# usb.net
KiCad netlist of a schematic drawn in Altium Designer
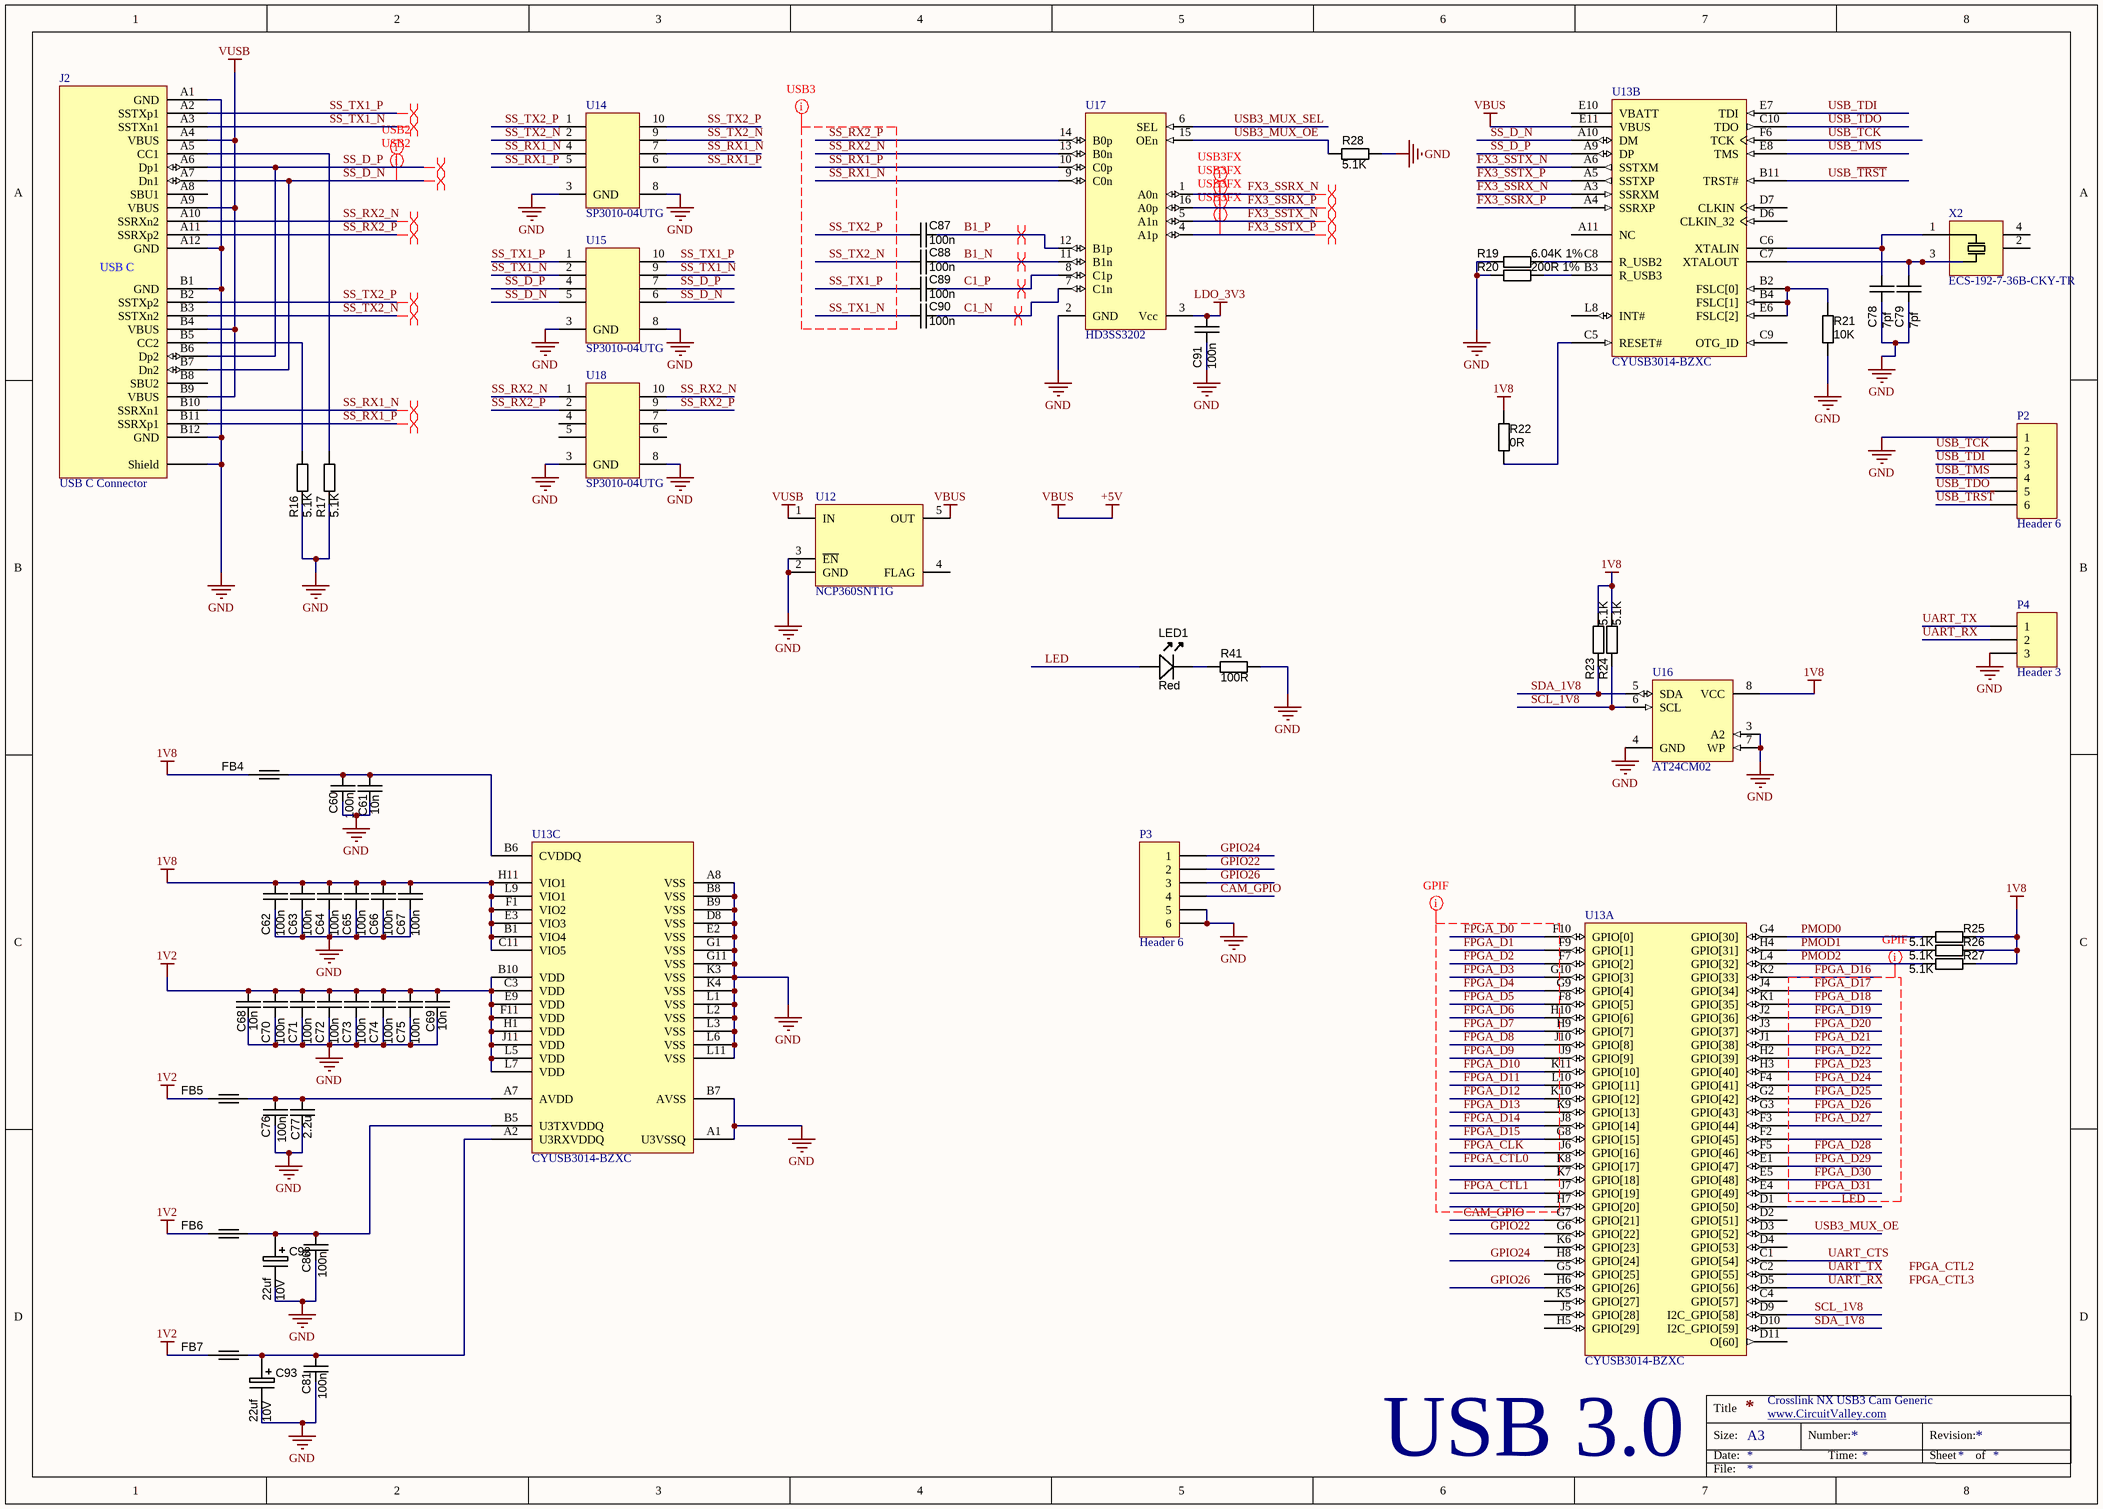
[diagram p0: usb.SchDoc]

(export (version "E")
  (design (tool "Eeschema 10.0.6"))
  (components
    (comp (ref "C60")
      (value "100n")
      (footprint "CAPC1608N")
      (description "Capacitor SMD Cer 10pF 5% 50V NP0 0603")
      (fields (field (name "TOLERANCE") "±5%") (field (name "PART") "C0603X104K5RAC"))
      (libsource (lib "PBL - Capacitors") (part "CAPC_10p_0603_NP0_1%_50V"))
    )
    (comp (ref "C61")
      (value "10n")
      (footprint "CAPC1608N")
      (description "Capacitor SMD Cer 10pF 5% 50V NP0 0603")
      (fields (field (name "TOLERANCE") "±5%") (field (name "PART") "C0603X104K5RAC"))
      (libsource (lib "PBL - Capacitors") (part "CAPC_10p_0603_NP0_1%_50V"))
    )
    (comp (ref "C62")
      (value "100n")
      (footprint "CAPC1608N")
      (description "Capacitor SMD Cer 10pF 5% 50V NP0 0603")
      (fields (field (name "TOLERANCE") "±5%") (field (name "PART") "C0603X104K5RAC"))
      (libsource (lib "PBL - Capacitors") (part "CAPC_10p_0603_NP0_1%_50V"))
    )
    (comp (ref "C63")
      (value "100n")
      (footprint "CAPC1608N")
      (description "Capacitor SMD Cer 10pF 5% 50V NP0 0603")
      (fields (field (name "TOLERANCE") "±5%") (field (name "PART") "C0603X104K5RAC"))
      (libsource (lib "PBL - Capacitors") (part "CAPC_10p_0603_NP0_1%_50V"))
    )
    (comp (ref "C64")
      (value "100n")
      (footprint "CAPC1608N")
      (description "Capacitor SMD Cer 10pF 5% 50V NP0 0603")
      (fields (field (name "TOLERANCE") "±5%") (field (name "PART") "C0603X104K5RAC"))
      (libsource (lib "PBL - Capacitors") (part "CAPC_10p_0603_NP0_1%_50V"))
    )
    (comp (ref "C65")
      (value "100n")
      (footprint "CAPC1608N")
      (description "Capacitor SMD Cer 10pF 5% 50V NP0 0603")
      (fields (field (name "TOLERANCE") "±5%") (field (name "PART") "C0603X104K5RAC"))
      (libsource (lib "PBL - Capacitors") (part "CAPC_10p_0603_NP0_1%_50V"))
    )
    (comp (ref "C66")
      (value "100n")
      (footprint "CAPC1608N")
      (description "Capacitor SMD Cer 10pF 5% 50V NP0 0603")
      (fields (field (name "TOLERANCE") "±5%") (field (name "PART") "C0603X104K5RAC"))
      (libsource (lib "PBL - Capacitors") (part "CAPC_10p_0603_NP0_1%_50V"))
    )
    (comp (ref "C67")
      (value "100n")
      (footprint "CAPC1608N")
      (description "Capacitor SMD Cer 10pF 5% 50V NP0 0603")
      (fields (field (name "TOLERANCE") "±5%") (field (name "PART") "C0603X104K5RAC"))
      (libsource (lib "PBL - Capacitors") (part "CAPC_10p_0603_NP0_1%_50V"))
    )
    (comp (ref "C68")
      (value "10n")
      (footprint "CAPC1608N")
      (description "Capacitor SMD Cer 10pF 5% 50V NP0 0603")
      (fields (field (name "TOLERANCE") "±5%") (field (name "PART") "C0603X104K5RAC"))
      (libsource (lib "PBL - Capacitors") (part "CAPC_10p_0603_NP0_1%_50V"))
    )
    (comp (ref "C69")
      (value "10n")
      (footprint "CAPC1608N")
      (description "Capacitor SMD Cer 10pF 5% 50V NP0 0603")
      (fields (field (name "TOLERANCE") "±5%") (field (name "PART") "C0603X104K5RAC"))
      (libsource (lib "PBL - Capacitors") (part "CAPC_10p_0603_NP0_1%_50V"))
    )
    (comp (ref "C70")
      (value "100n")
      (footprint "CAPC1608N")
      (description "Capacitor SMD Cer 10pF 5% 50V NP0 0603")
      (fields (field (name "TOLERANCE") "±5%") (field (name "PART") "C0603X104K5RAC"))
      (libsource (lib "PBL - Capacitors") (part "CAPC_10p_0603_NP0_1%_50V"))
    )
    (comp (ref "C71")
      (value "100n")
      (footprint "CAPC1608N")
      (description "Capacitor SMD Cer 10pF 5% 50V NP0 0603")
      (fields (field (name "TOLERANCE") "±5%") (field (name "PART") "C0603X104K5RAC"))
      (libsource (lib "PBL - Capacitors") (part "CAPC_10p_0603_NP0_1%_50V"))
    )
    (comp (ref "C72")
      (value "100n")
      (footprint "CAPC1608N")
      (description "Capacitor SMD Cer 10pF 5% 50V NP0 0603")
      (fields (field (name "TOLERANCE") "±5%") (field (name "PART") "C0603X104K5RAC"))
      (libsource (lib "PBL - Capacitors") (part "CAPC_10p_0603_NP0_1%_50V"))
    )
    (comp (ref "C73")
      (value "100n")
      (footprint "CAPC1608N")
      (description "Capacitor SMD Cer 10pF 5% 50V NP0 0603")
      (fields (field (name "TOLERANCE") "±5%") (field (name "PART") "C0603X104K5RAC"))
      (libsource (lib "PBL - Capacitors") (part "CAPC_10p_0603_NP0_1%_50V"))
    )
    (comp (ref "C74")
      (value "100n")
      (footprint "CAPC1608N")
      (description "Capacitor SMD Cer 10pF 5% 50V NP0 0603")
      (fields (field (name "TOLERANCE") "±5%") (field (name "PART") "C0603X104K5RAC"))
      (libsource (lib "PBL - Capacitors") (part "CAPC_10p_0603_NP0_1%_50V"))
    )
    (comp (ref "C75")
      (value "100n")
      (footprint "CAPC1608N")
      (description "Capacitor SMD Cer 10pF 5% 50V NP0 0603")
      (fields (field (name "TOLERANCE") "±5%") (field (name "PART") "C0603X104K5RAC"))
      (libsource (lib "PBL - Capacitors") (part "CAPC_10p_0603_NP0_1%_50V"))
    )
    (comp (ref "C76")
      (value "100n")
      (footprint "CAPC1608N")
      (description "Capacitor SMD Cer 10pF 5% 50V NP0 0603")
      (fields (field (name "TOLERANCE") "±5%") (field (name "PART") "C0603X104K5RAC"))
      (libsource (lib "PBL - Capacitors") (part "CAPC_10p_0603_NP0_1%_50V"))
    )
    (comp (ref "C77")
      (value "2.2u")
      (footprint "CAPC1608N")
      (description "Capacitor SMD Cer 10pF 5% 50V NP0 0603")
      (fields (field (name "TOLERANCE") "±5%") (field (name "PART") "C0603X104K5RAC"))
      (libsource (lib "PBL - Capacitors") (part "CAPC_10p_0603_NP0_1%_50V"))
    )
    (comp (ref "C78")
      (value "7pf")
      (footprint "CAPC1608N")
      (description "Capacitor SMD Cer 10pF 5% 50V NP0 0603")
      (fields (field (name "TOLERANCE") "±5%") (field (name "PART") "C0603X104K5RAC"))
      (libsource (lib "PBL - Capacitors") (part "CAPC_10p_0603_NP0_1%_50V"))
    )
    (comp (ref "C79")
      (value "7pf")
      (footprint "CAPC1608N")
      (description "Capacitor SMD Cer 10pF 5% 50V NP0 0603")
      (fields (field (name "TOLERANCE") "±5%") (field (name "PART") "C0603X104K5RAC"))
      (libsource (lib "PBL - Capacitors") (part "CAPC_10p_0603_NP0_1%_50V"))
    )
    (comp (ref "C80")
      (value "100n")
      (footprint "CAPC1608N")
      (description "Capacitor SMD Cer 10pF 5% 50V NP0 0603")
      (fields (field (name "TOLERANCE") "±5%") (field (name "PART") "C0603X104K5RAC"))
      (libsource (lib "PBL - Capacitors") (part "CAPC_10p_0603_NP0_1%_50V"))
    )
    (comp (ref "C81")
      (value "100n")
      (footprint "CAPC1608N")
      (description "Capacitor SMD Cer 10pF 5% 50V NP0 0603")
      (fields (field (name "TOLERANCE") "±5%") (field (name "PART") "C0603X104K5RAC"))
      (libsource (lib "PBL - Capacitors") (part "CAPC_10p_0603_NP0_1%_50V"))
    )
    (comp (ref "C87")
      (value "100n")
      (footprint "CAPC1005N")
      (description "Capacitor SMD Cer 10nF 10% 16V X7R 0402")
      (fields (field (name "TOLERANCE") "±10%"))
      (libsource (lib "PBL - Capacitors") (part "CAPC_10n_0402_16V_10%"))
    )
    (comp (ref "C88")
      (value "100n")
      (footprint "CAPC1005N")
      (description "Capacitor SMD Cer 10nF 10% 16V X7R 0402")
      (fields (field (name "TOLERANCE") "±10%"))
      (libsource (lib "PBL - Capacitors") (part "CAPC_10n_0402_16V_10%"))
    )
    (comp (ref "C89")
      (value "100n")
      (footprint "CAPC1005N")
      (description "Capacitor SMD Cer 10nF 10% 16V X7R 0402")
      (fields (field (name "TOLERANCE") "±10%"))
      (libsource (lib "PBL - Capacitors") (part "CAPC_10n_0402_16V_10%"))
    )
    (comp (ref "C90")
      (value "100n")
      (footprint "CAPC1005N")
      (description "Capacitor SMD Cer 10nF 10% 16V X7R 0402")
      (fields (field (name "TOLERANCE") "±10%"))
      (libsource (lib "PBL - Capacitors") (part "CAPC_10n_0402_16V_10%"))
    )
    (comp (ref "C91")
      (value "100n")
      (footprint "CAPC1608N")
      (description "Capacitor SMD Cer 10pF 5% 50V NP0 0603")
      (fields (field (name "TOLERANCE") "±5%") (field (name "PART") "C0603X104K5RAC"))
      (libsource (lib "PBL - Capacitors") (part "CAPC_10p_0603_NP0_1%_50V"))
    )
    (comp (ref "C92")
      (value "22uf")
      (footprint "CAPMP3528X210N")
      (description "Capacitor SMD Tantalum 47uF 20% 6.3V 1210")
      (fields (field (name "TOLERANCE") "±20%") (field (name "RATINGS") "10V"))
      (libsource (lib "PBL - Capacitors") (part "CAPT_47u_1210_6V3"))
    )
    (comp (ref "C93")
      (value "22uf")
      (footprint "CAPMP3528X210N")
      (description "Capacitor SMD Tantalum 47uF 20% 6.3V 1210")
      (fields (field (name "TOLERANCE") "±20%") (field (name "RATINGS") "10V"))
      (libsource (lib "PBL - Capacitors") (part "CAPT_47u_1210_6V3"))
    )
    (comp (ref "FB4")
      (value "~")
      (footprint "FBC2012N")
      (description "Ferrite bead 2.2K Ohm at 100 MHz 200mA 0805 SMD")
      (libsource (lib "PBL - Inductors") (part "FERRITE_0805"))
    )
    (comp (ref "FB5")
      (value "~")
      (footprint "FBC2012N")
      (description "Ferrite bead 2.2K Ohm at 100 MHz 200mA 0805 SMD")
      (libsource (lib "PBL - Inductors") (part "FERRITE_0805"))
    )
    (comp (ref "FB6")
      (value "~")
      (footprint "FBC2012N")
      (description "Ferrite bead 2.2K Ohm at 100 MHz 200mA 0805 SMD")
      (libsource (lib "PBL - Inductors") (part "FERRITE_0805"))
    )
    (comp (ref "FB7")
      (value "~")
      (footprint "FBC2012N")
      (description "Ferrite bead 2.2K Ohm at 100 MHz 200mA 0805 SMD")
      (libsource (lib "PBL - Inductors") (part "FERRITE_0805"))
    )
    (comp (ref "J2")
      (value "USB C Connector")
      (footprint "10137062-00021LF")
      (description "USB C connector")
      (libsource (lib "cvlib") (part "USB_C"))
    )
    (comp (ref "LED1")
      (value "Red")
      (footprint "LED-0603-RED")
      (description "LED 0603 SMD Hyper Red 630nm 220mcd 20mA")
      (libsource (lib "PBL - Light Sources") (part "LED_SMD_Red_0603_220mcd"))
    )
    (comp (ref "P2")
      (value "Header 6")
      (footprint "SMD_Solder_points_1.27")
      (description "Header, 6-Pin")
      (fields (field (name "PUBLISHER") "Altium Limited"))
      (libsource (lib "") (part "Header 6_1"))
    )
    (comp (ref "P3")
      (value "Header 6")
      (footprint "SMD_Solder_points_1.27")
      (description "Header, 6-Pin")
      (fields (field (name "PUBLISHER") "Altium Limited"))
      (libsource (lib "Miscellaneous Connectors") (part "Header 6"))
    )
    (comp (ref "P4")
      (value "Header 3")
      (footprint "SMD_3Solder_points_1.27")
      (description "Header, 3-Pin")
      (fields (field (name "PUBLISHER") "Altium Limited"))
      (libsource (lib "Miscellaneous Connectors") (part "Header 3"))
    )
    (comp (ref "R16")
      (value "5.1K")
      (footprint "RESC1608N_ZERO")
      (description "Resistor SMD chip 0.0 Ohm 0.1W 0603")
      (fields (field (name "TOLERANCE") "±5%") (field (name "Comment") "Thick Film"))
      (libsource (lib "") (part "RES_0R_0603_1"))
    )
    (comp (ref "R17")
      (value "5.1K")
      (footprint "RESC1608N_ZERO")
      (description "Resistor SMD chip 0.0 Ohm 0.1W 0603")
      (fields (field (name "TOLERANCE") "±5%") (field (name "Comment") "Thick Film"))
      (libsource (lib "") (part "RES_0R_0603_1"))
    )
    (comp (ref "R19")
      (value "6.04K 1%")
      (footprint "RESC1608N_ZERO")
      (description "Resistor SMD chip 0.0 Ohm 0.1W 0603")
      (fields (field (name "TOLERANCE") "±5%") (field (name "Comment") "Thick Film"))
      (libsource (lib "PBL - Resistors") (part "RES_0R_0603"))
    )
    (comp (ref "R20")
      (value "200R 1%")
      (footprint "RESC1608N_ZERO")
      (description "Resistor SMD chip 0.0 Ohm 0.1W 0603")
      (fields (field (name "TOLERANCE") "±5%") (field (name "Comment") "Thick Film"))
      (libsource (lib "PBL - Resistors") (part "RES_0R_0603"))
    )
    (comp (ref "R21")
      (value "10K")
      (footprint "RESC1608N_ZERO")
      (description "Resistor SMD chip 0.0 Ohm 0.1W 0603")
      (fields (field (name "TOLERANCE") "±5%") (field (name "Comment") "Thick Film"))
      (libsource (lib "") (part "RES_0R_0603_1"))
    )
    (comp (ref "R22")
      (value "0R")
      (footprint "RESC1608N_ZERO")
      (description "Resistor SMD chip 0.0 Ohm 0.1W 0603")
      (fields (field (name "TOLERANCE") "±5%") (field (name "Comment") "Thick Film"))
      (libsource (lib "") (part "RES_0R_0603_3"))
    )
    (comp (ref "R23")
      (value "5.1K")
      (footprint "RESC1608N_ZERO")
      (description "Resistor SMD chip 0.0 Ohm 0.1W 0603")
      (fields (field (name "TOLERANCE") "±5%") (field (name "Comment") "Thick Film"))
      (libsource (lib "") (part "RES_0R_0603_3"))
    )
    (comp (ref "R24")
      (value "5.1K")
      (footprint "RESC1608N_ZERO")
      (description "Resistor SMD chip 0.0 Ohm 0.1W 0603")
      (fields (field (name "TOLERANCE") "±5%") (field (name "Comment") "Thick Film"))
      (libsource (lib "") (part "RES_0R_0603_1"))
    )
    (comp (ref "R25")
      (value "5.1K")
      (footprint "RESC1608N_ZERO")
      (description "Resistor SMD chip 0.0 Ohm 0.1W 0603")
      (fields (field (name "TOLERANCE") "±5%") (field (name "Comment") "Thick Film"))
      (libsource (lib "") (part "RES_0R_0603_2"))
    )
    (comp (ref "R26")
      (value "5.1K")
      (footprint "RESC1608N_ZERO")
      (description "Resistor SMD chip 0.0 Ohm 0.1W 0603")
      (fields (field (name "TOLERANCE") "±5%") (field (name "Comment") "Thick Film"))
      (libsource (lib "") (part "RES_0R_0603_2"))
    )
    (comp (ref "R27")
      (value "5.1K")
      (footprint "RESC1608N_ZERO")
      (description "Resistor SMD chip 0.0 Ohm 0.1W 0603")
      (fields (field (name "TOLERANCE") "±5%") (field (name "Comment") "Thick Film"))
      (libsource (lib "") (part "RES_0R_0603_2"))
    )
    (comp (ref "R28")
      (value "5.1K")
      (footprint "RESC1608N_ZERO")
      (description "Resistor SMD chip 0.0 Ohm 0.1W 0603")
      (fields (field (name "TOLERANCE") "±5%") (field (name "Comment") "Thick Film"))
      (libsource (lib "") (part "RES_0R_0603_2"))
    )
    (comp (ref "R41")
      (value "100R")
      (footprint "RESC1608N_ZERO")
      (description "Resistor SMD chip 0.0 Ohm 0.1W 0603")
      (fields (field (name "TOLERANCE") "±5%") (field (name "Comment") "Thick Film"))
      (libsource (lib "") (part "RES_0R_0603_2"))
    )
    (comp (ref "U12")
      (value "NCP360SNT1G")
      (footprint "SOT23-5")
      (description "USB Overvoltage Protection")
      (libsource (lib "cvlib") (part "NCP360SNT1G"))
    )
    (comp (ref "U13")
      (value "CYUSB3014-BZXC")
      (footprint "CYP-BZX121")
      (description "EZ-USB(R) FX3: SuperSpeed USB Controller, 512 KB, 60 I/Os, 0 to 70 degC, 121-Pin FBGA (BZX121)")
      (fields (field (name "MANUFACTURER") "Cypress"))
      (libsource (lib "") (part "CYUSB3014-BZXC_1"))
    )
    (comp (ref "U14")
      (value "SP3010-04UTG")
      (footprint "uDFN-10")
      (description "ESD Protection")
      (libsource (lib "cvlib") (part "SP3010-04UTG"))
    )
    (comp (ref "U15")
      (value "SP3010-04UTG")
      (footprint "uDFN-10")
      (description "ESD Protection")
      (libsource (lib "cvlib") (part "SP3010-04UTG"))
    )
    (comp (ref "U16")
      (value "AT24CM02")
      (footprint "SOIC8")
      (description "2Mbit I2C EEPROM")
      (libsource (lib "cvlib") (part "AT24CM02"))
    )
    (comp (ref "U17")
      (value "HD3SS3202")
      (footprint "UQFN-16")
      (description "USB 3.0 Mux")
      (libsource (lib "cvlib") (part "HD3SS3202"))
    )
    (comp (ref "U18")
      (value "SP3010-04UTG")
      (footprint "uDFN-10")
      (description "ESD Protection")
      (libsource (lib "cvlib") (part "SP3010-04UTG"))
    )
    (comp (ref "X2")
      (value "ECS-192-7-36B-CKY-TR")
      (footprint "Active Oscillator 2520")
      (description "Crystal Oscillator")
      (libsource (lib "cvlib") (part "Crystal"))
    )
  )
  (nets
    (net (code "1") (name "+5V") (class "Default")
      (node (ref "U12") (pin "5") (pinfunction "OUT_5") (pintype "power_in"))
      (node (ref "U13") (pin "E11") (pinfunction "VBUS_E11") (pintype "power_in"))
    )
    (net (code "2") (name "/B1_N") (class "Default")
      (node (ref "C88") (pin "2") (pintype "passive"))
      (node (ref "U17") (pin "11") (pinfunction "B1n_11") (pintype "bidirectional"))
    )
    (net (code "3") (name "/B1_P") (class "Default")
      (node (ref "C87") (pin "2") (pintype "passive"))
      (node (ref "U17") (pin "12") (pinfunction "B1p_12") (pintype "bidirectional"))
    )
    (net (code "4") (name "/C1_N") (class "Default")
      (node (ref "C90") (pin "2") (pintype "passive"))
      (node (ref "U17") (pin "7") (pinfunction "C1n_7") (pintype "bidirectional"))
    )
    (net (code "5") (name "/C1_P") (class "Default")
      (node (ref "C89") (pin "2") (pintype "passive"))
      (node (ref "U17") (pin "8") (pinfunction "C1p_8") (pintype "bidirectional"))
    )
    (net (code "6") (name "/CAM_GPIO") (class "Default")
      (node (ref "P3") (pin "4") (pinfunction "4_4") (pintype "passive"))
      (node (ref "U13") (pin "G7") (pinfunction "GPIO[21]_G7") (pintype "bidirectional"))
    )
    (net (code "7") (name "/FPGA_CLK") (class "Default")
      (node (ref "U13") (pin "J6") (pinfunction "GPIO[16]_J6") (pintype "bidirectional"))
    )
    (net (code "8") (name "/FPGA_CTL0") (class "Default")
      (node (ref "U13") (pin "K8") (pinfunction "GPIO[17]_K8") (pintype "bidirectional"))
    )
    (net (code "9") (name "/FPGA_CTL1") (class "Default")
      (node (ref "U13") (pin "J7") (pinfunction "GPIO[19]_J7") (pintype "bidirectional"))
    )
    (net (code "12") (name "/FPGA_D0") (class "Default")
      (node (ref "U13") (pin "F10") (pinfunction "GPIO[0]_F10") (pintype "bidirectional"))
    )
    (net (code "13") (name "/FPGA_D1") (class "Default")
      (node (ref "U13") (pin "F9") (pinfunction "GPIO[1]_F9") (pintype "bidirectional"))
    )
    (net (code "14") (name "/FPGA_D2") (class "Default")
      (node (ref "U13") (pin "F7") (pinfunction "GPIO[2]_F7") (pintype "bidirectional"))
    )
    (net (code "15") (name "/FPGA_D3") (class "Default")
      (node (ref "U13") (pin "G10") (pinfunction "GPIO[3]_G10") (pintype "bidirectional"))
    )
    (net (code "16") (name "/FPGA_D4") (class "Default")
      (node (ref "U13") (pin "G9") (pinfunction "GPIO[4]_G9") (pintype "bidirectional"))
    )
    (net (code "17") (name "/FPGA_D5") (class "Default")
      (node (ref "U13") (pin "F8") (pinfunction "GPIO[5]_F8") (pintype "bidirectional"))
    )
    (net (code "18") (name "/FPGA_D6") (class "Default")
      (node (ref "U13") (pin "H10") (pinfunction "GPIO[6]_H10") (pintype "bidirectional"))
    )
    (net (code "19") (name "/FPGA_D7") (class "Default")
      (node (ref "U13") (pin "H9") (pinfunction "GPIO[7]_H9") (pintype "bidirectional"))
    )
    (net (code "20") (name "/FPGA_D8") (class "Default")
      (node (ref "U13") (pin "J10") (pinfunction "GPIO[8]_J10") (pintype "bidirectional"))
    )
    (net (code "21") (name "/FPGA_D9") (class "Default")
      (node (ref "U13") (pin "J9") (pinfunction "GPIO[9]_J9") (pintype "bidirectional"))
    )
    (net (code "22") (name "/FPGA_D10") (class "Default")
      (node (ref "U13") (pin "K11") (pinfunction "GPIO[10]_K11") (pintype "bidirectional"))
    )
    (net (code "23") (name "/FPGA_D11") (class "Default")
      (node (ref "U13") (pin "L10") (pinfunction "GPIO[11]_L10") (pintype "bidirectional"))
    )
    (net (code "24") (name "/FPGA_D12") (class "Default")
      (node (ref "U13") (pin "K10") (pinfunction "GPIO[12]_K10") (pintype "bidirectional"))
    )
    (net (code "25") (name "/FPGA_D13") (class "Default")
      (node (ref "U13") (pin "K9") (pinfunction "GPIO[13]_K9") (pintype "bidirectional"))
    )
    (net (code "26") (name "/FPGA_D14") (class "Default")
      (node (ref "U13") (pin "J8") (pinfunction "GPIO[14]_J8") (pintype "bidirectional"))
    )
    (net (code "27") (name "/FPGA_D15") (class "Default")
      (node (ref "U13") (pin "G8") (pinfunction "GPIO[15]_G8") (pintype "bidirectional"))
    )
    (net (code "28") (name "/FPGA_D16") (class "Default")
      (node (ref "U13") (pin "K2") (pinfunction "GPIO[33]_K2") (pintype "bidirectional"))
    )
    (net (code "29") (name "/FPGA_D17") (class "Default")
      (node (ref "U13") (pin "J4") (pinfunction "GPIO[34]_J4") (pintype "bidirectional"))
    )
    (net (code "30") (name "/FPGA_D18") (class "Default")
      (node (ref "U13") (pin "K1") (pinfunction "GPIO[35]_K1") (pintype "bidirectional"))
    )
    (net (code "31") (name "/FPGA_D19") (class "Default")
      (node (ref "U13") (pin "J2") (pinfunction "GPIO[36]_J2") (pintype "bidirectional"))
    )
    (net (code "32") (name "/FPGA_D20") (class "Default")
      (node (ref "U13") (pin "J3") (pinfunction "GPIO[37]_J3") (pintype "bidirectional"))
    )
    (net (code "33") (name "/FPGA_D21") (class "Default")
      (node (ref "U13") (pin "J1") (pinfunction "GPIO[38]_J1") (pintype "bidirectional"))
    )
    (net (code "34") (name "/FPGA_D22") (class "Default")
      (node (ref "U13") (pin "H2") (pinfunction "GPIO[39]_H2") (pintype "bidirectional"))
    )
    (net (code "35") (name "/FPGA_D23") (class "Default")
      (node (ref "U13") (pin "H3") (pinfunction "GPIO[40]_H3") (pintype "bidirectional"))
    )
    (net (code "36") (name "/FPGA_D24") (class "Default")
      (node (ref "U13") (pin "F4") (pinfunction "GPIO[41]_F4") (pintype "bidirectional"))
    )
    (net (code "37") (name "/FPGA_D25") (class "Default")
      (node (ref "U13") (pin "G2") (pinfunction "GPIO[42]_G2") (pintype "bidirectional"))
    )
    (net (code "38") (name "/FPGA_D26") (class "Default")
      (node (ref "U13") (pin "G3") (pinfunction "GPIO[43]_G3") (pintype "bidirectional"))
    )
    (net (code "39") (name "/FPGA_D27") (class "Default")
      (node (ref "U13") (pin "F3") (pinfunction "GPIO[44]_F3") (pintype "bidirectional"))
    )
    (net (code "40") (name "/FPGA_D28") (class "Default")
      (node (ref "U13") (pin "F5") (pinfunction "GPIO[46]_F5") (pintype "bidirectional"))
    )
    (net (code "41") (name "/FPGA_D29") (class "Default")
      (node (ref "U13") (pin "E1") (pinfunction "GPIO[47]_E1") (pintype "bidirectional"))
    )
    (net (code "42") (name "/FPGA_D30") (class "Default")
      (node (ref "U13") (pin "E5") (pinfunction "GPIO[48]_E5") (pintype "bidirectional"))
    )
    (net (code "43") (name "/FPGA_D31") (class "Default")
      (node (ref "U13") (pin "E4") (pinfunction "GPIO[49]_E4") (pintype "bidirectional"))
    )
    (net (code "44") (name "/FX3_SSRX_N") (class "Default")
      (node (ref "U13") (pin "A3") (pinfunction "SSRXM_A3") (pintype "input"))
      (node (ref "U17") (pin "1") (pinfunction "A0n_1") (pintype "bidirectional"))
    )
    (net (code "45") (name "/FX3_SSRX_P") (class "Default")
      (node (ref "U13") (pin "A4") (pinfunction "SSRXP_A4") (pintype "input"))
      (node (ref "U17") (pin "16") (pinfunction "A0p_16") (pintype "bidirectional"))
    )
    (net (code "46") (name "/FX3_SSTX_N") (class "Default")
      (node (ref "U13") (pin "A6") (pinfunction "SSTXM_A6") (pintype "output"))
      (node (ref "U17") (pin "5") (pinfunction "A1n_5") (pintype "bidirectional"))
    )
    (net (code "47") (name "/FX3_SSTX_P") (class "Default")
      (node (ref "U13") (pin "A5") (pinfunction "SSTXP_A5") (pintype "output"))
      (node (ref "U17") (pin "4") (pinfunction "A1p_4") (pintype "bidirectional"))
    )
    (net (code "48") (name "/GPIO22") (class "Default")
      (node (ref "P3") (pin "2") (pinfunction "2_2") (pintype "passive"))
      (node (ref "U13") (pin "G6") (pinfunction "GPIO[22]_G6") (pintype "bidirectional"))
    )
    (net (code "49") (name "/GPIO24") (class "Default")
      (node (ref "P3") (pin "1") (pinfunction "1_1") (pintype "passive"))
      (node (ref "U13") (pin "H8") (pinfunction "GPIO[24]_H8") (pintype "bidirectional"))
    )
    (net (code "50") (name "/GPIO26") (class "Default")
      (node (ref "P3") (pin "3") (pinfunction "3_3") (pintype "passive"))
      (node (ref "U13") (pin "H6") (pinfunction "GPIO[26]_H6") (pintype "bidirectional"))
    )
    (net (code "51") (name "/LED") (class "Default")
      (node (ref "LED1") (pin "A") (pinfunction "A_A") (pintype "passive"))
      (node (ref "U13") (pin "D1") (pinfunction "GPIO[50]_D1") (pintype "bidirectional"))
    )
    (net (code "52") (name "/PMOD0") (class "Default")
      (node (ref "R25") (pin "1") (pinfunction "1_1") (pintype "passive"))
      (node (ref "U13") (pin "G4") (pinfunction "GPIO[30]_G4") (pintype "bidirectional"))
    )
    (net (code "53") (name "/PMOD1") (class "Default")
      (node (ref "R26") (pin "1") (pinfunction "1_1") (pintype "passive"))
      (node (ref "U13") (pin "H4") (pinfunction "GPIO[31]_H4") (pintype "bidirectional"))
    )
    (net (code "54") (name "/PMOD2") (class "Default")
      (node (ref "R27") (pin "1") (pinfunction "1_1") (pintype "passive"))
      (node (ref "U13") (pin "L4") (pinfunction "GPIO[32]_L4") (pintype "bidirectional"))
    )
    (net (code "55") (name "/SCL_1V8") (class "Default")
      (node (ref "R24") (pin "2") (pinfunction "2_2") (pintype "passive"))
      (node (ref "U13") (pin "D9") (pinfunction "I2C_GPIO[58]_D9") (pintype "bidirectional"))
      (node (ref "U16") (pin "6") (pinfunction "SCL_6") (pintype "input"))
    )
    (net (code "56") (name "/SDA_1V8") (class "Default")
      (node (ref "R23") (pin "1") (pinfunction "1_1") (pintype "passive"))
      (node (ref "U13") (pin "D10") (pinfunction "I2C_GPIO[59]_D10") (pintype "bidirectional"))
      (node (ref "U16") (pin "5") (pinfunction "SDA_5") (pintype "bidirectional"))
    )
    (net (code "57") (name "/SS_D_N") (class "Default")
      (node (ref "J2") (pin "A7") (pinfunction "Dn1_A7") (pintype "bidirectional"))
      (node (ref "J2") (pin "B7") (pinfunction "Dn2_B7") (pintype "bidirectional"))
      (node (ref "U13") (pin "A10") (pinfunction "DM_A10") (pintype "bidirectional"))
      (node (ref "U15") (pin "5") (pintype "passive"))
      (node (ref "U15") (pin "6") (pintype "passive"))
    )
    (net (code "58") (name "/SS_D_P") (class "Default")
      (node (ref "J2") (pin "A6") (pinfunction "Dp1_A6") (pintype "bidirectional"))
      (node (ref "J2") (pin "B6") (pinfunction "Dp2_B6") (pintype "bidirectional"))
      (node (ref "U13") (pin "A9") (pinfunction "DP_A9") (pintype "bidirectional"))
      (node (ref "U15") (pin "4") (pintype "passive"))
      (node (ref "U15") (pin "7") (pintype "passive"))
    )
    (net (code "59") (name "/SS_RX1_N") (class "Default")
      (node (ref "J2") (pin "B10") (pinfunction "SSRXn1_B10") (pintype "passive"))
      (node (ref "U14") (pin "4") (pintype "passive"))
      (node (ref "U14") (pin "7") (pintype "passive"))
      (node (ref "U17") (pin "9") (pinfunction "C0n_9") (pintype "bidirectional"))
    )
    (net (code "60") (name "/SS_RX1_P") (class "Default")
      (node (ref "J2") (pin "B11") (pinfunction "SSRXp1_B11") (pintype "passive"))
      (node (ref "U14") (pin "5") (pintype "passive"))
      (node (ref "U14") (pin "6") (pintype "passive"))
      (node (ref "U17") (pin "10") (pinfunction "C0p_10") (pintype "bidirectional"))
    )
    (net (code "61") (name "/SS_RX2_N") (class "Default")
      (node (ref "J2") (pin "A10") (pinfunction "SSRXn2_A10") (pintype "passive"))
      (node (ref "U17") (pin "13") (pinfunction "B0n_13") (pintype "bidirectional"))
      (node (ref "U18") (pin "1") (pintype "passive"))
      (node (ref "U18") (pin "10") (pintype "passive"))
    )
    (net (code "62") (name "/SS_RX2_P") (class "Default")
      (node (ref "J2") (pin "A11") (pinfunction "SSRXp2_A11") (pintype "passive"))
      (node (ref "U17") (pin "14") (pinfunction "B0p_14") (pintype "bidirectional"))
      (node (ref "U18") (pin "2") (pintype "passive"))
      (node (ref "U18") (pin "9") (pintype "passive"))
    )
    (net (code "63") (name "/SS_TX1_N") (class "Default")
      (node (ref "C90") (pin "1") (pintype "passive"))
      (node (ref "J2") (pin "A3") (pinfunction "SSTXn1_A3") (pintype "passive"))
      (node (ref "U15") (pin "2") (pintype "passive"))
      (node (ref "U15") (pin "9") (pintype "passive"))
    )
    (net (code "64") (name "/SS_TX1_P") (class "Default")
      (node (ref "C89") (pin "1") (pintype "passive"))
      (node (ref "J2") (pin "A2") (pinfunction "SSTXp1_A2") (pintype "passive"))
      (node (ref "U15") (pin "1") (pintype "passive"))
      (node (ref "U15") (pin "10") (pintype "passive"))
    )
    (net (code "65") (name "/SS_TX2_N") (class "Default")
      (node (ref "C88") (pin "1") (pintype "passive"))
      (node (ref "J2") (pin "B3") (pinfunction "SSTXn2_B3") (pintype "passive"))
      (node (ref "U14") (pin "2") (pintype "passive"))
      (node (ref "U14") (pin "9") (pintype "passive"))
    )
    (net (code "66") (name "/SS_TX2_P") (class "Default")
      (node (ref "C87") (pin "1") (pintype "passive"))
      (node (ref "J2") (pin "B2") (pinfunction "SSTXp2_B2") (pintype "passive"))
      (node (ref "U14") (pin "1") (pintype "passive"))
      (node (ref "U14") (pin "10") (pintype "passive"))
    )
    (net (code "67") (name "/UART_CTS") (class "Default")
      (node (ref "U13") (pin "C1") (pinfunction "GPIO[54]_C1") (pintype "bidirectional"))
    )
    (net (code "68") (name "/UART_RX") (class "Default")
      (node (ref "P4") (pin "2") (pinfunction "2_2") (pintype "passive"))
      (node (ref "U13") (pin "D5") (pinfunction "GPIO[56]_D5") (pintype "bidirectional"))
    )
    (net (code "69") (name "/UART_TX") (class "Default")
      (node (ref "P4") (pin "1") (pinfunction "1_1") (pintype "passive"))
      (node (ref "U13") (pin "C2") (pinfunction "GPIO[55]_C2") (pintype "bidirectional"))
    )
    (net (code "70") (name "/USB3_MUX_OE") (class "Default")
      (node (ref "R28") (pin "1") (pinfunction "1_1") (pintype "passive"))
      (node (ref "U13") (pin "D3") (pinfunction "GPIO[52]_D3") (pintype "bidirectional"))
      (node (ref "U17") (pin "15") (pinfunction "OEn_15") (pintype "input"))
    )
    (net (code "71") (name "/USB3_MUX_SEL") (class "Default")
      (node (ref "U17") (pin "6") (pinfunction "SEL_6") (pintype "input"))
    )
    (net (code "72") (name "/USB_TCK") (class "Default")
      (node (ref "P2") (pin "2") (pinfunction "2_2") (pintype "passive"))
      (node (ref "U13") (pin "F6") (pinfunction "TCK_F6") (pintype "input"))
    )
    (net (code "73") (name "/USB_TDI") (class "Default")
      (node (ref "P2") (pin "3") (pinfunction "3_3") (pintype "passive"))
      (node (ref "U13") (pin "E7") (pinfunction "TDI_E7") (pintype "input"))
    )
    (net (code "74") (name "/USB_TDO") (class "Default")
      (node (ref "P2") (pin "5") (pinfunction "5_5") (pintype "passive"))
      (node (ref "U13") (pin "C10") (pinfunction "TDO_C10") (pintype "output"))
    )
    (net (code "75") (name "/USB_TMS") (class "Default")
      (node (ref "P2") (pin "4") (pinfunction "4_4") (pintype "passive"))
      (node (ref "U13") (pin "E8") (pinfunction "TMS_E8") (pintype "input"))
    )
    (net (code "76") (name "/USB_~{TRST}") (class "Default")
      (node (ref "P2") (pin "6") (pinfunction "6_6") (pintype "passive"))
      (node (ref "U13") (pin "B11") (pinfunction "TRST#_B11") (pintype "input"))
    )
    (net (code "77") (name "1V2") (class "Default")
      (node (ref "C68") (pin "2") (pintype "passive"))
      (node (ref "C69") (pin "2") (pintype "passive"))
      (node (ref "C70") (pin "2") (pintype "passive"))
      (node (ref "C71") (pin "2") (pintype "passive"))
      (node (ref "C72") (pin "2") (pintype "passive"))
      (node (ref "C73") (pin "2") (pintype "passive"))
      (node (ref "C74") (pin "2") (pintype "passive"))
      (node (ref "C75") (pin "2") (pintype "passive"))
      (node (ref "FB5") (pin "1") (pinfunction "1_1") (pintype "passive"))
      (node (ref "FB6") (pin "1") (pinfunction "1_1") (pintype "passive"))
      (node (ref "FB7") (pin "1") (pinfunction "1_1") (pintype "passive"))
      (node (ref "U13") (pin "B10") (pinfunction "VDD_B10") (pintype "power_in"))
      (node (ref "U13") (pin "C3") (pinfunction "VDD_C3") (pintype "power_in"))
      (node (ref "U13") (pin "E9") (pinfunction "VDD_E9") (pintype "power_in"))
      (node (ref "U13") (pin "F11") (pinfunction "VDD_F11") (pintype "power_in"))
      (node (ref "U13") (pin "H1") (pinfunction "VDD_H1") (pintype "power_in"))
      (node (ref "U13") (pin "J11") (pinfunction "VDD_J11") (pintype "power_in"))
      (node (ref "U13") (pin "L5") (pinfunction "VDD_L5") (pintype "power_in"))
      (node (ref "U13") (pin "L7") (pinfunction "VDD_L7") (pintype "power_in"))
    )
    (net (code "78") (name "1V8") (class "Default")
      (node (ref "C62") (pin "2") (pintype "passive"))
      (node (ref "C63") (pin "2") (pintype "passive"))
      (node (ref "C64") (pin "2") (pintype "passive"))
      (node (ref "C65") (pin "2") (pintype "passive"))
      (node (ref "C66") (pin "2") (pintype "passive"))
      (node (ref "C67") (pin "2") (pintype "passive"))
      (node (ref "FB4") (pin "1") (pinfunction "1_1") (pintype "passive"))
      (node (ref "R22") (pin "2") (pinfunction "2_2") (pintype "passive"))
      (node (ref "R23") (pin "2") (pinfunction "2_2") (pintype "passive"))
      (node (ref "R24") (pin "1") (pinfunction "1_1") (pintype "passive"))
      (node (ref "R25") (pin "2") (pinfunction "2_2") (pintype "passive"))
      (node (ref "R26") (pin "2") (pinfunction "2_2") (pintype "passive"))
      (node (ref "R27") (pin "2") (pinfunction "2_2") (pintype "passive"))
      (node (ref "U13") (pin "B1") (pinfunction "VIO4_B1") (pintype "power_in"))
      (node (ref "U13") (pin "C11") (pinfunction "VIO5_C11") (pintype "power_in"))
      (node (ref "U13") (pin "E3") (pinfunction "VIO3_E3") (pintype "power_in"))
      (node (ref "U13") (pin "F1") (pinfunction "VIO2_F1") (pintype "power_in"))
      (node (ref "U13") (pin "H11") (pinfunction "VIO1_H11") (pintype "power_in"))
      (node (ref "U13") (pin "L9") (pinfunction "VIO1_L9") (pintype "power_in"))
      (node (ref "U16") (pin "8") (pinfunction "VCC_8") (pintype "power_in"))
    )
    (net (code "79") (name "GND") (class "Default")
      (node (ref "C60") (pin "1") (pintype "passive"))
      (node (ref "C61") (pin "1") (pintype "passive"))
      (node (ref "C62") (pin "1") (pintype "passive"))
      (node (ref "C63") (pin "1") (pintype "passive"))
      (node (ref "C64") (pin "1") (pintype "passive"))
      (node (ref "C65") (pin "1") (pintype "passive"))
      (node (ref "C66") (pin "1") (pintype "passive"))
      (node (ref "C67") (pin "1") (pintype "passive"))
      (node (ref "C68") (pin "1") (pintype "passive"))
      (node (ref "C69") (pin "1") (pintype "passive"))
      (node (ref "C70") (pin "1") (pintype "passive"))
      (node (ref "C71") (pin "1") (pintype "passive"))
      (node (ref "C72") (pin "1") (pintype "passive"))
      (node (ref "C73") (pin "1") (pintype "passive"))
      (node (ref "C74") (pin "1") (pintype "passive"))
      (node (ref "C75") (pin "1") (pintype "passive"))
      (node (ref "C76") (pin "1") (pintype "passive"))
      (node (ref "C77") (pin "1") (pintype "passive"))
      (node (ref "C78") (pin "1") (pintype "passive"))
      (node (ref "C79") (pin "1") (pintype "passive"))
      (node (ref "C80") (pin "1") (pintype "passive"))
      (node (ref "C81") (pin "1") (pintype "passive"))
      (node (ref "C91") (pin "1") (pintype "passive"))
      (node (ref "C92") (pin "2") (pintype "passive"))
      (node (ref "C93") (pin "2") (pintype "passive"))
      (node (ref "J2") (pin "0") (pinfunction "Shield_0") (pintype "power_in"))
      (node (ref "J2") (pin "A1") (pinfunction "GND_A1") (pintype "power_in"))
      (node (ref "J2") (pin "A12") (pinfunction "GND_A12") (pintype "power_in"))
      (node (ref "J2") (pin "B1") (pinfunction "GND_B1") (pintype "power_in"))
      (node (ref "J2") (pin "B12") (pinfunction "GND_B12") (pintype "power_in"))
      (node (ref "P2") (pin "1") (pinfunction "1_1") (pintype "passive"))
      (node (ref "P3") (pin "5") (pinfunction "5_5") (pintype "passive"))
      (node (ref "P3") (pin "6") (pinfunction "6_6") (pintype "passive"))
      (node (ref "P4") (pin "3") (pinfunction "3_3") (pintype "passive"))
      (node (ref "R16") (pin "2") (pinfunction "2_2") (pintype "passive"))
      (node (ref "R17") (pin "2") (pinfunction "2_2") (pintype "passive"))
      (node (ref "R19") (pin "2") (pinfunction "2_2") (pintype "passive"))
      (node (ref "R20") (pin "2") (pinfunction "2_2") (pintype "passive"))
      (node (ref "R21") (pin "2") (pinfunction "2_2") (pintype "passive"))
      (node (ref "R28") (pin "2") (pinfunction "2_2") (pintype "passive"))
      (node (ref "R41") (pin "2") (pinfunction "2_2") (pintype "passive"))
      (node (ref "U12") (pin "2") (pinfunction "GND_2") (pintype "power_in"))
      (node (ref "U12") (pin "3") (pinfunction "~{EN}_3") (pintype "power_in"))
      (node (ref "U13") (pin "A1") (pinfunction "U3VSSQ_A1") (pintype "power_in"))
      (node (ref "U13") (pin "A8") (pinfunction "VSS_A8") (pintype "power_in"))
      (node (ref "U13") (pin "B7") (pinfunction "AVSS_B7") (pintype "power_in"))
      (node (ref "U13") (pin "B8") (pinfunction "VSS_B8") (pintype "power_in"))
      (node (ref "U13") (pin "B9") (pinfunction "VSS_B9") (pintype "power_in"))
      (node (ref "U13") (pin "D8") (pinfunction "VSS_D8") (pintype "power_in"))
      (node (ref "U13") (pin "E2") (pinfunction "VSS_E2") (pintype "power_in"))
      (node (ref "U13") (pin "G1") (pinfunction "VSS_G1") (pintype "power_in"))
      (node (ref "U13") (pin "G11") (pinfunction "VSS_G11") (pintype "power_in"))
      (node (ref "U13") (pin "K3") (pinfunction "VSS_K3") (pintype "power_in"))
      (node (ref "U13") (pin "K4") (pinfunction "VSS_K4") (pintype "power_in"))
      (node (ref "U13") (pin "L1") (pinfunction "VSS_L1") (pintype "power_in"))
      (node (ref "U13") (pin "L11") (pinfunction "VSS_L11") (pintype "power_in"))
      (node (ref "U13") (pin "L2") (pinfunction "VSS_L2") (pintype "power_in"))
      (node (ref "U13") (pin "L3") (pinfunction "VSS_L3") (pintype "power_in"))
      (node (ref "U13") (pin "L6") (pinfunction "VSS_L6") (pintype "power_in"))
      (node (ref "U14") (pin "3") (pinfunction "GND_3") (pintype "passive"))
      (node (ref "U14") (pin "8") (pinfunction "GND_8") (pintype "passive"))
      (node (ref "U15") (pin "3") (pinfunction "GND_3") (pintype "passive"))
      (node (ref "U15") (pin "8") (pinfunction "GND_8") (pintype "passive"))
      (node (ref "U16") (pin "3") (pinfunction "A2_3") (pintype "input"))
      (node (ref "U16") (pin "4") (pinfunction "GND_4") (pintype "power_in"))
      (node (ref "U16") (pin "7") (pinfunction "WP_7") (pintype "input"))
      (node (ref "U17") (pin "2") (pinfunction "GND_2") (pintype "power_in"))
      (node (ref "U18") (pin "3") (pinfunction "GND_3") (pintype "passive"))
      (node (ref "U18") (pin "8") (pinfunction "GND_8") (pintype "passive"))
    )
    (net (code "80") (name "LDO_3V3") (class "Default")
      (node (ref "C91") (pin "2") (pintype "passive"))
      (node (ref "U17") (pin "3") (pinfunction "Vcc_3") (pintype "power_in"))
    )
    (net (code "81") (name "Net-(J2-CC1)") (class "Default")
      (node (ref "J2") (pin "A5") (pinfunction "CC1_A5") (pintype "power_in"))
      (node (ref "R17") (pin "1") (pinfunction "1_1") (pintype "passive"))
    )
    (net (code "82") (name "Net-(J2-CC2)") (class "Default")
      (node (ref "J2") (pin "B5") (pinfunction "CC2_B5") (pintype "power_in"))
      (node (ref "R16") (pin "1") (pinfunction "1_1") (pintype "passive"))
    )
    (net (code "83") (name "Net-(LED1-PadK)") (class "Default")
      (node (ref "LED1") (pin "K") (pinfunction "K_K") (pintype "passive"))
      (node (ref "R41") (pin "1") (pinfunction "1_1") (pintype "passive"))
    )
    (net (code "84") (name "Net-(U13B-FSLC[0])") (class "Default")
      (node (ref "R21") (pin "1") (pinfunction "1_1") (pintype "passive"))
      (node (ref "U13") (pin "B2") (pinfunction "FSLC[0]_B2") (pintype "input"))
      (node (ref "U13") (pin "B4") (pinfunction "FSLC[1]_B4") (pintype "input"))
      (node (ref "U13") (pin "E6") (pinfunction "FSLC[2]_E6") (pintype "input"))
    )
    (net (code "85") (name "Net-(U13B-RESET#)") (class "Default")
      (node (ref "R22") (pin "1") (pinfunction "1_1") (pintype "passive"))
      (node (ref "U13") (pin "C5") (pinfunction "RESET#_C5") (pintype "input"))
    )
    (net (code "86") (name "Net-(U13B-R_USB2)") (class "Default")
      (node (ref "R19") (pin "1") (pinfunction "1_1") (pintype "passive"))
      (node (ref "U13") (pin "C8") (pinfunction "R_USB2_C8") (pintype "passive"))
    )
    (net (code "87") (name "Net-(U13B-R_USB3)") (class "Default")
      (node (ref "R20") (pin "1") (pinfunction "1_1") (pintype "passive"))
      (node (ref "U13") (pin "B3") (pinfunction "R_USB3_B3") (pintype "passive"))
    )
    (net (code "88") (name "Net-(U13B-XTALIN)") (class "Default")
      (node (ref "C78") (pin "2") (pintype "passive"))
      (node (ref "U13") (pin "C6") (pinfunction "XTALIN_C6") (pintype "passive"))
      (node (ref "X2") (pin "1") (pinfunction "X1_1") (pintype "passive"))
    )
    (net (code "89") (name "Net-(U13B-XTALOUT)") (class "Default")
      (node (ref "C79") (pin "2") (pintype "passive"))
      (node (ref "U13") (pin "C7") (pinfunction "XTALOUT_C7") (pintype "passive"))
      (node (ref "X2") (pin "3") (pinfunction "X2_3") (pintype "passive"))
    )
    (net (code "90") (name "Net-(U13C-AVDD)") (class "Default")
      (node (ref "C76") (pin "2") (pintype "passive"))
      (node (ref "C77") (pin "2") (pintype "passive"))
      (node (ref "FB5") (pin "2") (pinfunction "2_2") (pintype "passive"))
      (node (ref "U13") (pin "A7") (pinfunction "AVDD_A7") (pintype "power_in"))
    )
    (net (code "91") (name "Net-(U13C-CVDDQ)") (class "Default")
      (node (ref "C60") (pin "2") (pintype "passive"))
      (node (ref "C61") (pin "2") (pintype "passive"))
      (node (ref "FB4") (pin "2") (pinfunction "2_2") (pintype "passive"))
      (node (ref "U13") (pin "B6") (pinfunction "CVDDQ_B6") (pintype "power_in"))
    )
    (net (code "92") (name "Net-(U13C-U3RXVDDQ)") (class "Default")
      (node (ref "C81") (pin "2") (pintype "passive"))
      (node (ref "C93") (pin "1") (pintype "passive"))
      (node (ref "FB7") (pin "2") (pinfunction "2_2") (pintype "passive"))
      (node (ref "U13") (pin "A2") (pinfunction "U3RXVDDQ_A2") (pintype "power_in"))
    )
    (net (code "93") (name "Net-(U13C-U3TXVDDQ)") (class "Default")
      (node (ref "C80") (pin "2") (pintype "passive"))
      (node (ref "C92") (pin "1") (pintype "passive"))
      (node (ref "FB6") (pin "2") (pinfunction "2_2") (pintype "passive"))
      (node (ref "U13") (pin "B5") (pinfunction "U3TXVDDQ_B5") (pintype "power_in"))
    )
    (net (code "94") (name "VUSB") (class "Default")
      (node (ref "J2") (pin "A4") (pinfunction "VBUS_A4") (pintype "power_in"))
      (node (ref "J2") (pin "A9") (pinfunction "VBUS_A9") (pintype "power_in"))
      (node (ref "J2") (pin "B4") (pinfunction "VBUS_B4") (pintype "power_in"))
      (node (ref "J2") (pin "B9") (pinfunction "VBUS_B9") (pintype "power_in"))
      (node (ref "U12") (pin "1") (pinfunction "IN_1") (pintype "power_in"))
    )
    (net (code "95") (name "unconnected-(J2-SBU1-PadA8)") (class "Default")
      (node (ref "J2") (pin "A8") (pinfunction "SBU1_A8") (pintype "power_in"))
    )
    (net (code "96") (name "unconnected-(J2-SBU2-PadB8)") (class "Default")
      (node (ref "J2") (pin "B8") (pinfunction "SBU2_B8") (pintype "power_in"))
    )
    (net (code "97") (name "unconnected-(U12-FLAG-Pad4)") (class "Default")
      (node (ref "U12") (pin "4") (pinfunction "FLAG_4") (pintype "power_in"))
    )
    (net (code "98") (name "unconnected-(U13A-GPIO[18]-PadK7)") (class "Default")
      (node (ref "U13") (pin "K7") (pinfunction "GPIO[18]_K7") (pintype "bidirectional"))
    )
    (net (code "99") (name "unconnected-(U13A-GPIO[20]-PadH7)") (class "Default")
      (node (ref "U13") (pin "H7") (pinfunction "GPIO[20]_H7") (pintype "bidirectional"))
    )
    (net (code "100") (name "unconnected-(U13A-GPIO[23]-PadK6)") (class "Default")
      (node (ref "U13") (pin "K6") (pinfunction "GPIO[23]_K6") (pintype "bidirectional"))
    )
    (net (code "101") (name "unconnected-(U13A-GPIO[25]-PadG5)") (class "Default")
      (node (ref "U13") (pin "G5") (pinfunction "GPIO[25]_G5") (pintype "bidirectional"))
    )
    (net (code "102") (name "unconnected-(U13A-GPIO[27]-PadK5)") (class "Default")
      (node (ref "U13") (pin "K5") (pinfunction "GPIO[27]_K5") (pintype "bidirectional"))
    )
    (net (code "103") (name "unconnected-(U13A-GPIO[28]-PadJ5)") (class "Default")
      (node (ref "U13") (pin "J5") (pinfunction "GPIO[28]_J5") (pintype "bidirectional"))
    )
    (net (code "104") (name "unconnected-(U13A-GPIO[29]-PadH5)") (class "Default")
      (node (ref "U13") (pin "H5") (pinfunction "GPIO[29]_H5") (pintype "bidirectional"))
    )
    (net (code "105") (name "unconnected-(U13A-GPIO[45]-PadF2)") (class "Default")
      (node (ref "U13") (pin "F2") (pinfunction "GPIO[45]_F2") (pintype "bidirectional"))
    )
    (net (code "106") (name "unconnected-(U13A-GPIO[51]-PadD2)") (class "Default")
      (node (ref "U13") (pin "D2") (pinfunction "GPIO[51]_D2") (pintype "bidirectional"))
    )
    (net (code "107") (name "unconnected-(U13A-GPIO[53]-PadD4)") (class "Default")
      (node (ref "U13") (pin "D4") (pinfunction "GPIO[53]_D4") (pintype "bidirectional"))
    )
    (net (code "108") (name "unconnected-(U13A-GPIO[57]-PadC4)") (class "Default")
      (node (ref "U13") (pin "C4") (pinfunction "GPIO[57]_C4") (pintype "bidirectional"))
    )
    (net (code "109") (name "unconnected-(U13A-O[60]-PadD11)") (class "Default")
      (node (ref "U13") (pin "D11") (pinfunction "O[60]_D11") (pintype "output"))
    )
    (net (code "110") (name "unconnected-(U13B-CLKIN-PadD7)") (class "Default")
      (node (ref "U13") (pin "D7") (pinfunction "CLKIN_D7") (pintype "input"))
    )
    (net (code "111") (name "unconnected-(U13B-CLKIN_32-PadD6)") (class "Default")
      (node (ref "U13") (pin "D6") (pinfunction "CLKIN_32_D6") (pintype "input"))
    )
    (net (code "112") (name "unconnected-(U13B-INT#-PadL8)") (class "Default")
      (node (ref "U13") (pin "L8") (pinfunction "INT#_L8") (pintype "bidirectional"))
    )
    (net (code "113") (name "unconnected-(U13B-NC-PadA11)") (class "Default")
      (node (ref "U13") (pin "A11") (pinfunction "NC_A11") (pintype "passive"))
    )
    (net (code "114") (name "unconnected-(U13B-OTG_ID-PadC9)") (class "Default")
      (node (ref "U13") (pin "C9") (pinfunction "OTG_ID_C9") (pintype "input"))
    )
    (net (code "115") (name "unconnected-(U13B-VBATT-PadE10)") (class "Default")
      (node (ref "U13") (pin "E10") (pinfunction "VBATT_E10") (pintype "power_in"))
    )
    (net (code "116") (name "unconnected-(U18-Pad4)") (class "Default")
      (node (ref "U18") (pin "4") (pintype "passive"))
    )
    (net (code "117") (name "unconnected-(U18-Pad5)") (class "Default")
      (node (ref "U18") (pin "5") (pintype "passive"))
    )
    (net (code "118") (name "unconnected-(U18-Pad6)") (class "Default")
      (node (ref "U18") (pin "6") (pintype "passive"))
    )
    (net (code "119") (name "unconnected-(U18-Pad7)") (class "Default")
      (node (ref "U18") (pin "7") (pintype "passive"))
    )
    (net (code "120") (name "unconnected-(X2-NC-Pad2)") (class "Default")
      (node (ref "X2") (pin "2") (pinfunction "NC_2") (pintype "passive"))
    )
    (net (code "121") (name "unconnected-(X2-NC-Pad4)") (class "Default")
      (node (ref "X2") (pin "4") (pinfunction "NC_4") (pintype "passive"))
    )
  )
)
